# DCMotor2CTRL.net
KiCad netlist of a schematic drawn in Altium Designer
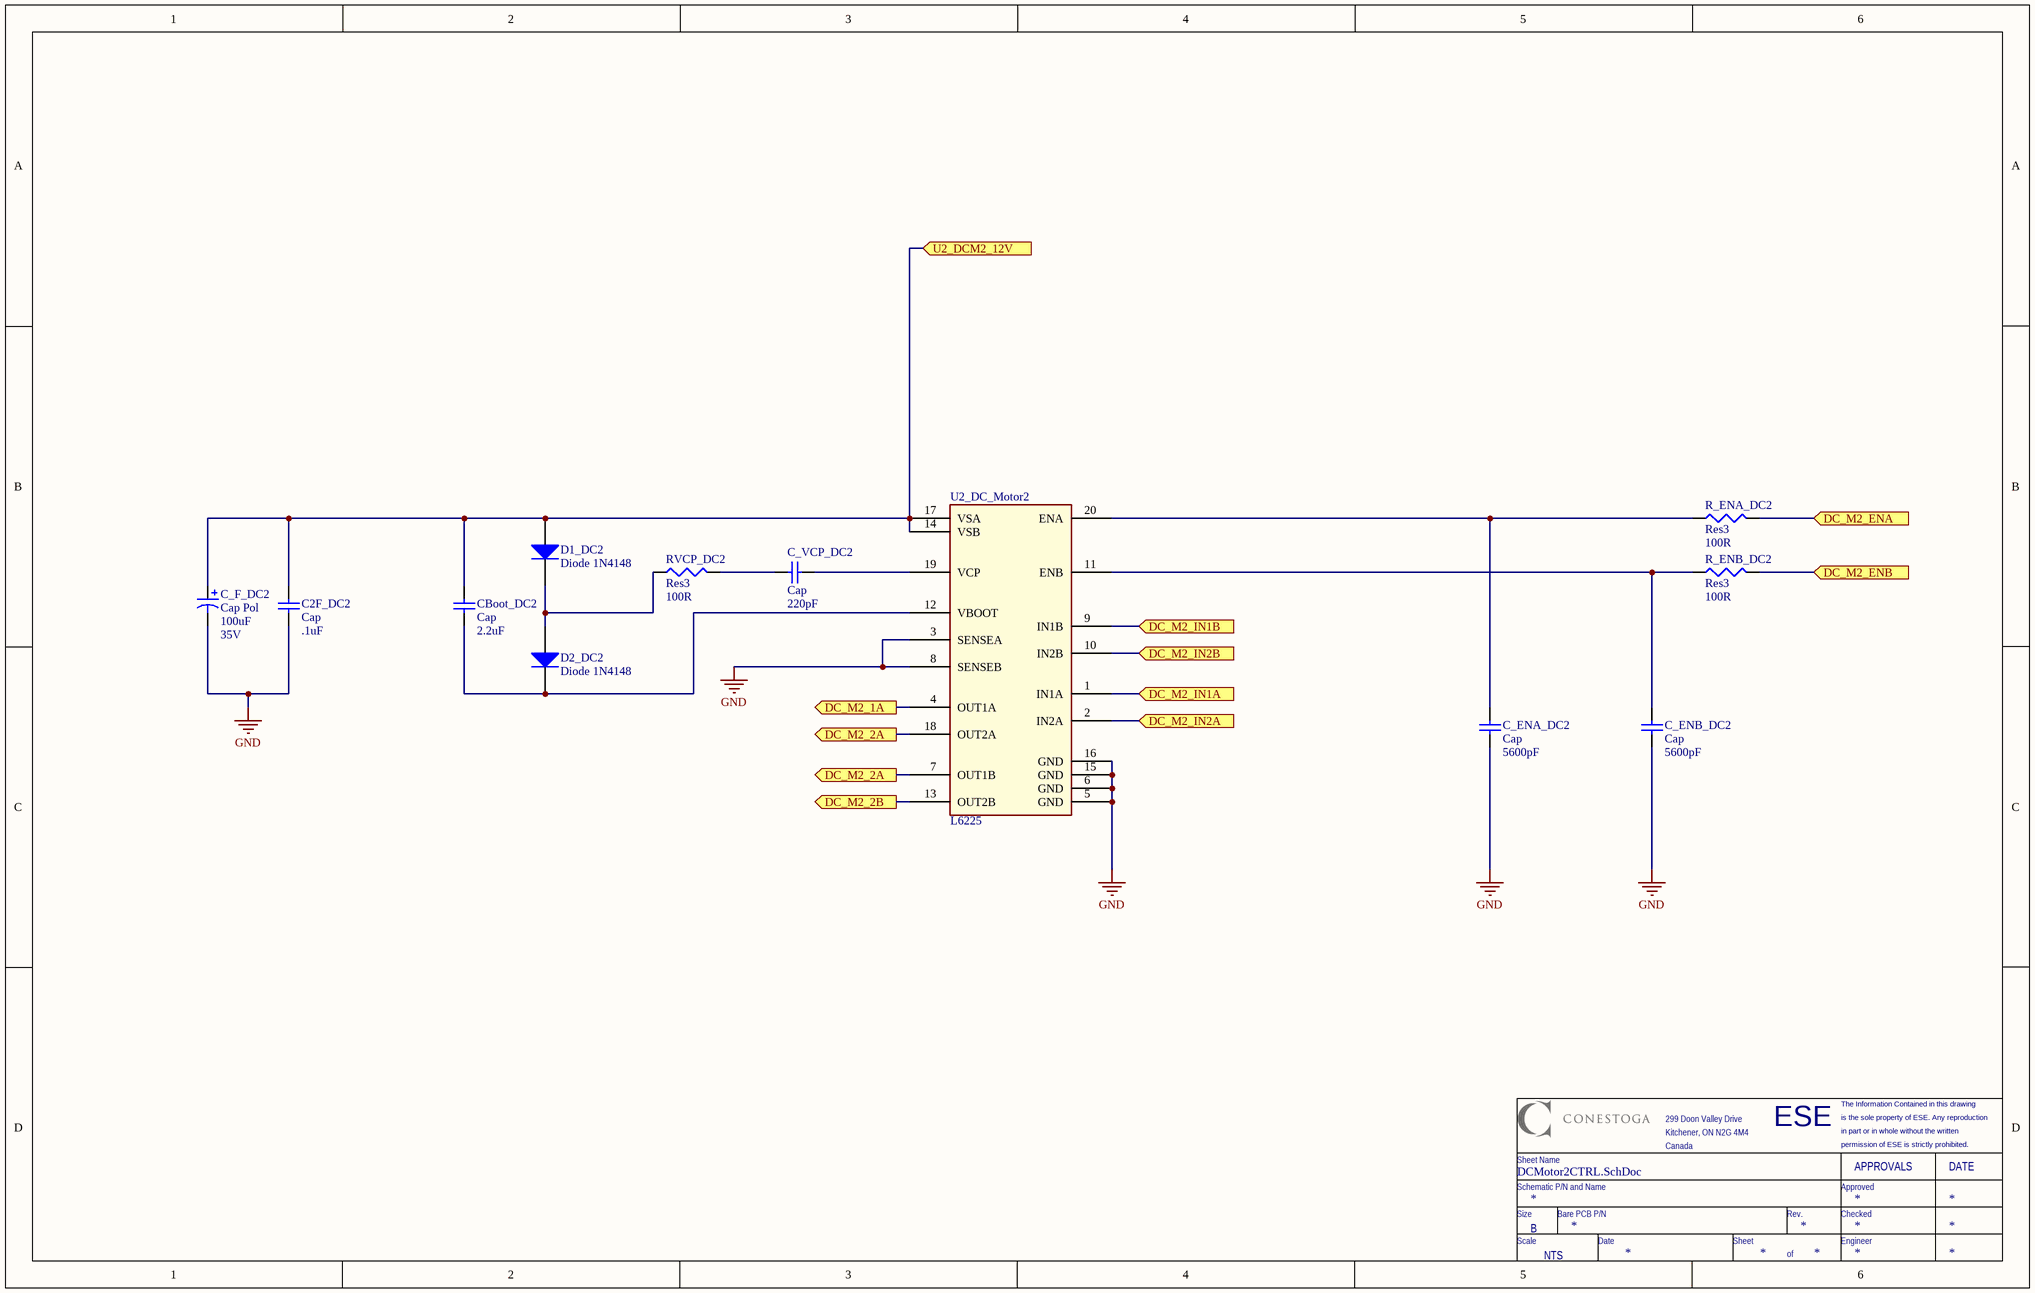
[diagram p0: DCMotor2CTRL.SchDoc]

(export (version "E")
  (design (tool "Eeschema 10.0.6"))
  (components
    (comp (ref "C2F_DC2")
      (value "Cap")
      (footprint "CAPC2012X09M")
      (description "CAP CER .1uF 100v X7R 0805")
      (fields (field (name "ALTIUM_VALUE") ".1uF") (field (name "MPN") "C0805C104K1RACTU"))
      (libsource (lib "esd_library") (part "CAP-X7R-.1uF-100V-±10%"))
    )
    (comp (ref "CBoot_DC2")
      (value "Cap")
      (footprint "CAPC2012X09M")
      (description "CAP CER 2.2uF 16v X7R 0805")
      (fields (field (name "ALTIUM_VALUE") "2.2uF") (field (name "MPN") "C0805C225K4RACTU"))
      (libsource (lib "esd_library") (part "CAP-X7R-2.2uF-16V-±10%"))
    )
    (comp (ref "C_ENA_DC2")
      (value "Cap")
      (footprint "CAPC2012X09M")
      (description "CAP CER 5600pF 50v X7R 0805")
      (fields (field (name "ALTIUM_VALUE") "5600pF") (field (name "MPN") "C0805C562K5RACTU"))
      (libsource (lib "esd_library") (part "CAP-X7R-5600pF-50V-±10%"))
    )
    (comp (ref "C_ENB_DC2")
      (value "Cap")
      (footprint "CAPC2012X09M")
      (description "CAP CER 5600pF 50v X7R 0805")
      (fields (field (name "ALTIUM_VALUE") "5600pF") (field (name "MPN") "C0805C562K5RACTU"))
      (libsource (lib "esd_library") (part "CAP-X7R-5600pF-50V-±10%"))
    )
    (comp (ref "C_F_DC2")
      (value "Cap Pol")
      (footprint "CAPACITOR_6.3MM")
      (description "CAP 85C 100uF ±20% 16V WX Series Aluminum Electrolytic")
      (fields
        (field (name "ALTIUM_VALUE") "100uF")
        (field (name "VOLTAGE") "35V")
        (field (name "MPN") "UWX1C101MCL1GB")
      )
      (libsource (lib "esd_library") (part "Cap Polar-100uF-16V"))
    )
    (comp (ref "C_VCP_DC2")
      (value "Cap")
      (footprint "CAPC2012X09M")
      (description "CAP CER 220pF 50v COG 0805")
      (fields (field (name "ALTIUM_VALUE") "220pF") (field (name "MPN") "C0805C221J5GACTU"))
      (libsource (lib "Caps$") (part "CAP-COG-220pF-50V-±5%"))
    )
    (comp (ref "D1_DC2")
      (value "Diode 1N4148")
      (footprint "zener_sod323")
      (description "High Conductance Fast Diode")
      (libsource (lib "esd_library") (part "Diode 1N4148"))
    )
    (comp (ref "D2_DC2")
      (value "Diode 1N4148")
      (footprint "zener_sod323")
      (description "High Conductance Fast Diode")
      (libsource (lib "esd_library") (part "Diode 1N4148"))
    )
    (comp (ref "RVCP_DC2")
      (value "Res3")
      (footprint "RESC2112X05M")
      (description "RES SMD 100R OHM 1% 1/8W 0805")
      (fields (field (name "ALTIUM_VALUE") "100R") (field (name "MPN") "CRCW0805100RFKEA"))
      (libsource (lib "esd_library") (part "Resistor_100R"))
    )
    (comp (ref "R_ENA_DC2")
      (value "Res3")
      (footprint "RESC2112X05M")
      (description "RES SMD 100R OHM 1% 1/8W 0805")
      (fields (field (name "ALTIUM_VALUE") "100R") (field (name "MPN") "CRCW0805100RFKEA"))
      (libsource (lib "esd_library") (part "Resistor_100R"))
    )
    (comp (ref "R_ENB_DC2")
      (value "Res3")
      (footprint "RESC2112X05M")
      (description "RES SMD 100R OHM 1% 1/8W 0805")
      (fields (field (name "ALTIUM_VALUE") "100R") (field (name "MPN") "CRCW0805100RFKEA"))
      (libsource (lib "esd_library") (part "Resistor_100R"))
    )
    (comp (ref "U2_DC_Motor2")
      (value "L6225")
      (footprint "POWERSOP20")
      (description "IC MOTOR DRIVER PAR 20POWERSO")
      (fields (field (name "MPN") "L6225PDTR"))
      (libsource (lib "esd_library") (part "L6225"))
    )
  )
  (nets
    (net (code "1") (name "/DC_M2_1A") (class "Default")
      (node (ref "U2_DC_Motor2") (pin "4") (pinfunction "OUT1A_4") (pintype "passive"))
    )
    (net (code "2") (name "/DC_M2_2A") (class "Default")
      (node (ref "U2_DC_Motor2") (pin "18") (pinfunction "OUT2A_18") (pintype "passive"))
      (node (ref "U2_DC_Motor2") (pin "7") (pinfunction "OUT1B_7") (pintype "passive"))
    )
    (net (code "3") (name "/DC_M2_2B") (class "Default")
      (node (ref "U2_DC_Motor2") (pin "13") (pinfunction "OUT2B_13") (pintype "passive"))
    )
    (net (code "4") (name "/DC_M2_ENA") (class "Default")
      (node (ref "R_ENA_DC2") (pin "2") (pinfunction "2_2") (pintype "passive"))
    )
    (net (code "5") (name "/DC_M2_ENB") (class "Default")
      (node (ref "R_ENB_DC2") (pin "2") (pinfunction "2_2") (pintype "passive"))
    )
    (net (code "6") (name "/DC_M2_IN1A") (class "Default")
      (node (ref "U2_DC_Motor2") (pin "1") (pinfunction "IN1A_1") (pintype "passive"))
    )
    (net (code "7") (name "/DC_M2_IN1B") (class "Default")
      (node (ref "U2_DC_Motor2") (pin "9") (pinfunction "IN1B_9") (pintype "passive"))
    )
    (net (code "8") (name "/DC_M2_IN2A") (class "Default")
      (node (ref "U2_DC_Motor2") (pin "2") (pinfunction "IN2A_2") (pintype "passive"))
    )
    (net (code "9") (name "/DC_M2_IN2B") (class "Default")
      (node (ref "U2_DC_Motor2") (pin "10") (pinfunction "IN2B_10") (pintype "passive"))
    )
    (net (code "10") (name "/U2_DCM2_12V") (class "Default")
      (node (ref "C2F_DC2") (pin "2") (pinfunction "2_2") (pintype "passive"))
      (node (ref "CBoot_DC2") (pin "2") (pinfunction "2_2") (pintype "passive"))
      (node (ref "C_F_DC2") (pin "1") (pinfunction "1_1") (pintype "passive"))
      (node (ref "D1_DC2") (pin "A") (pinfunction "A_A") (pintype "passive"))
      (node (ref "U2_DC_Motor2") (pin "14") (pinfunction "VSB_14") (pintype "power_in"))
      (node (ref "U2_DC_Motor2") (pin "17") (pinfunction "VSA_17") (pintype "power_in"))
    )
    (net (code "11") (name "GND") (class "Default")
      (node (ref "C2F_DC2") (pin "1") (pinfunction "1_1") (pintype "passive"))
      (node (ref "C_ENA_DC2") (pin "1") (pinfunction "1_1") (pintype "passive"))
      (node (ref "C_ENB_DC2") (pin "1") (pinfunction "1_1") (pintype "passive"))
      (node (ref "C_F_DC2") (pin "2") (pinfunction "2_2") (pintype "passive"))
      (node (ref "U2_DC_Motor2") (pin "15") (pinfunction "GND_15") (pintype "power_in"))
      (node (ref "U2_DC_Motor2") (pin "16") (pinfunction "GND_16") (pintype "power_in"))
      (node (ref "U2_DC_Motor2") (pin "3") (pinfunction "SENSEA_3") (pintype "open_collector"))
      (node (ref "U2_DC_Motor2") (pin "5") (pinfunction "GND_5") (pintype "power_in"))
      (node (ref "U2_DC_Motor2") (pin "6") (pinfunction "GND_6") (pintype "power_in"))
      (node (ref "U2_DC_Motor2") (pin "8") (pinfunction "SENSEB_8") (pintype "power_in"))
    )
    (net (code "12") (name "Net-(C_VCP_DC2-Pad1)") (class "Default")
      (node (ref "C_VCP_DC2") (pin "1") (pinfunction "1_1") (pintype "passive"))
      (node (ref "RVCP_DC2") (pin "2") (pinfunction "2_2") (pintype "passive"))
    )
    (net (code "13") (name "Net-(D1_DC2-PadK)") (class "Default")
      (node (ref "D1_DC2") (pin "K") (pinfunction "K_K") (pintype "passive"))
      (node (ref "D2_DC2") (pin "A") (pinfunction "A_A") (pintype "passive"))
      (node (ref "RVCP_DC2") (pin "1") (pinfunction "1_1") (pintype "passive"))
    )
    (net (code "14") (name "Net-(U2_DC_Motor2-ENA)") (class "Default")
      (node (ref "C_ENA_DC2") (pin "2") (pinfunction "2_2") (pintype "passive"))
      (node (ref "R_ENA_DC2") (pin "1") (pinfunction "1_1") (pintype "passive"))
      (node (ref "U2_DC_Motor2") (pin "20") (pinfunction "ENA_20") (pintype "passive"))
    )
    (net (code "15") (name "Net-(U2_DC_Motor2-ENB)") (class "Default")
      (node (ref "C_ENB_DC2") (pin "2") (pinfunction "2_2") (pintype "passive"))
      (node (ref "R_ENB_DC2") (pin "1") (pinfunction "1_1") (pintype "passive"))
      (node (ref "U2_DC_Motor2") (pin "11") (pinfunction "ENB_11") (pintype "passive"))
    )
    (net (code "16") (name "Net-(U2_DC_Motor2-VBOOT)") (class "Default")
      (node (ref "CBoot_DC2") (pin "1") (pinfunction "1_1") (pintype "passive"))
      (node (ref "D2_DC2") (pin "K") (pinfunction "K_K") (pintype "passive"))
      (node (ref "U2_DC_Motor2") (pin "12") (pinfunction "VBOOT_12") (pintype "power_in"))
    )
    (net (code "17") (name "Net-(U2_DC_Motor2-VCP)") (class "Default")
      (node (ref "C_VCP_DC2") (pin "2") (pinfunction "2_2") (pintype "passive"))
      (node (ref "U2_DC_Motor2") (pin "19") (pinfunction "VCP_19") (pintype "power_in"))
    )
  )
)
